# shield_schematic.net
KiCad netlist of a schematic drawn in EAGLE
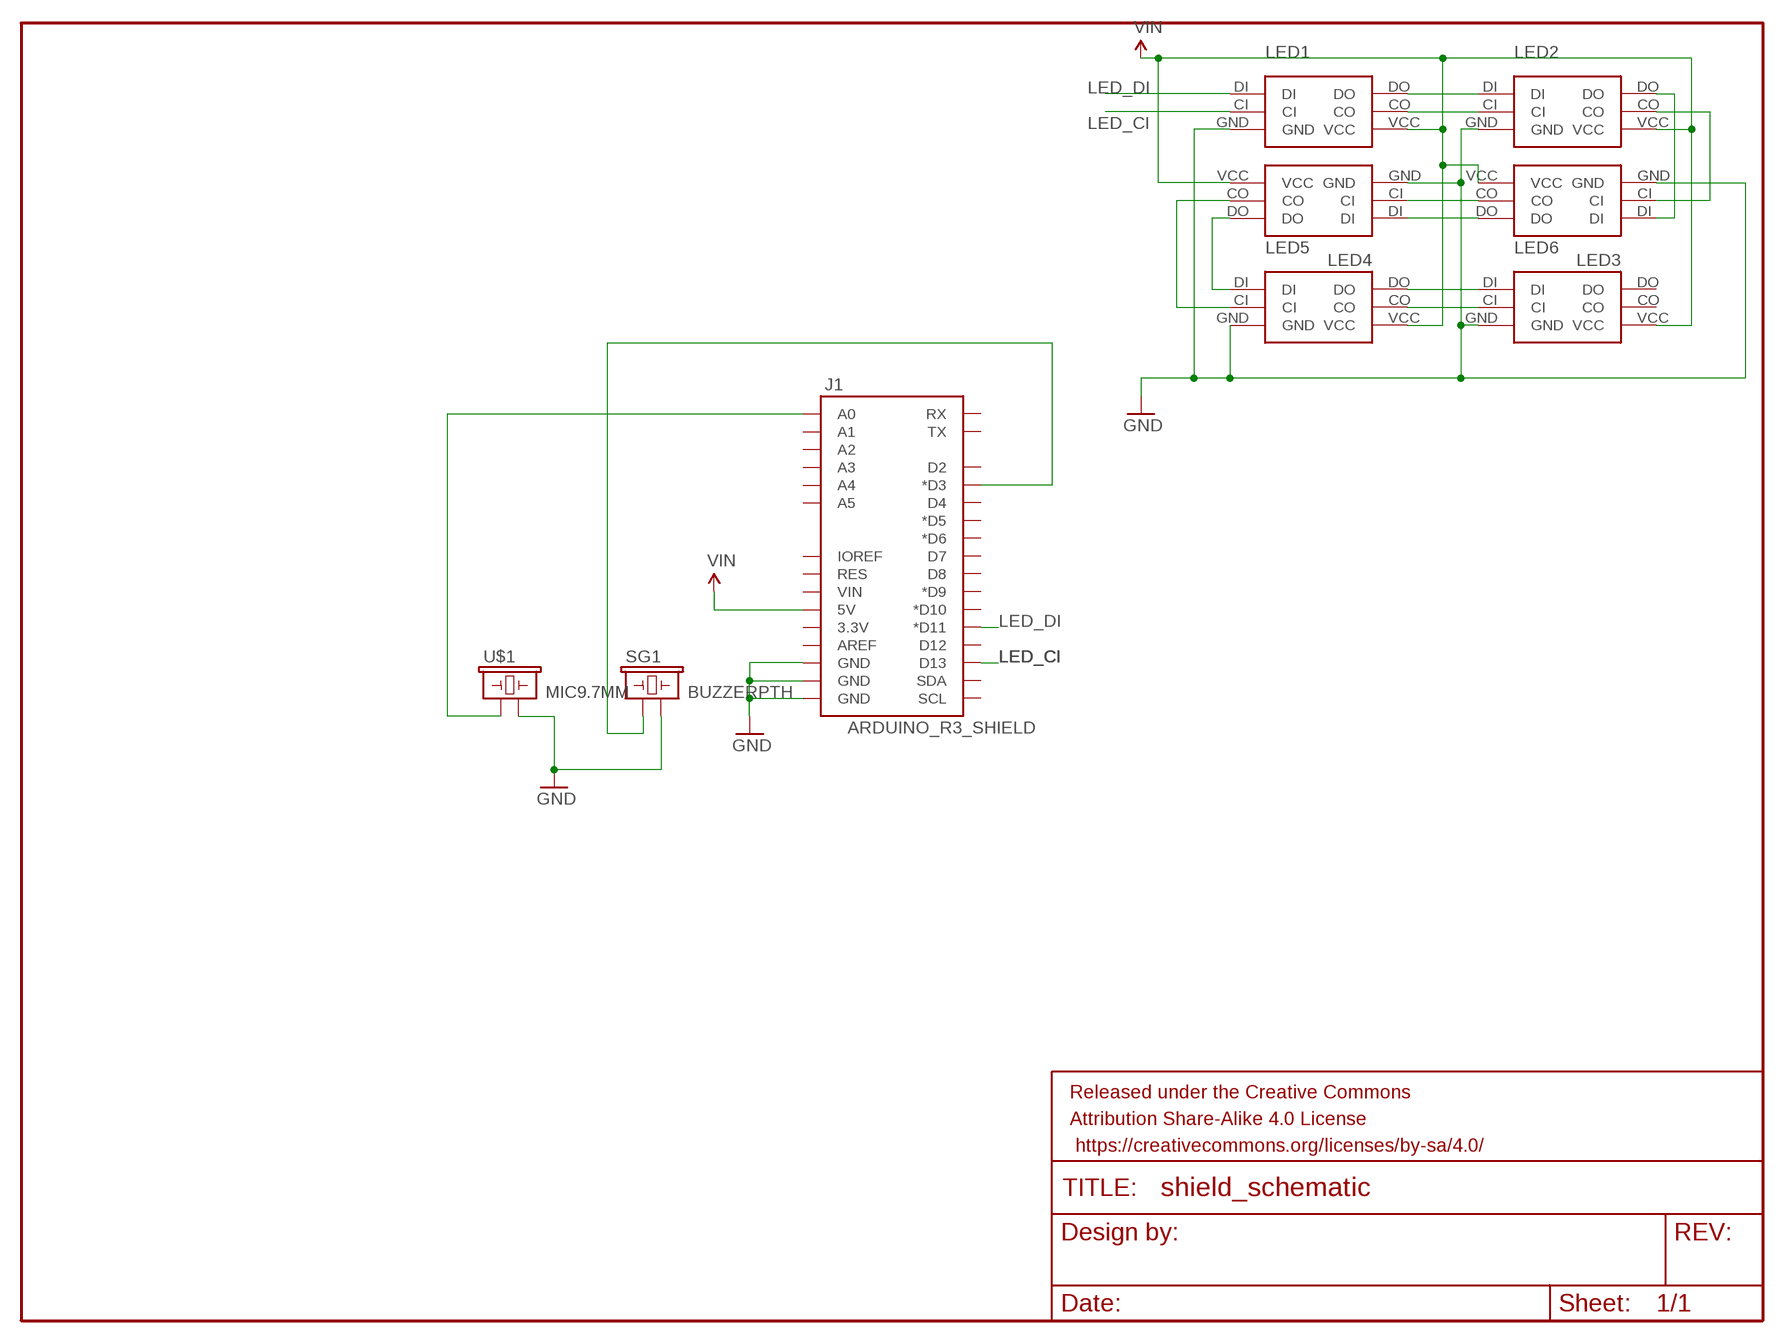
[diagram p0: schematic, sheet 1]

(export (version "E")
  (design (tool "Eeschema 10.0.6"))
  (components
    (comp (ref "FRAME1")
      (value "FRAME-LETTER")
      (footprint "eagle-import:CREATIVE_COMMONS")
      (libsource (lib "eagle-import") (part "FRAME-LETTER"))
    )
    (comp (ref "J1")
      (value "ARDUINO_R3_SHIELD")
      (footprint "eagle-import:UNO_R3_SHIELD")
      (libsource (lib "eagle-import") (part "ARDUINO_R3_SHIELD"))
    )
    (comp (ref "LED1")
      (value "APA102SMD")
      (footprint "eagle-import:RGBLED5050")
      (libsource (lib "eagle-import") (part "APA102SMD"))
    )
    (comp (ref "LED2")
      (value "APA102SMD")
      (footprint "eagle-import:RGBLED5050")
      (libsource (lib "eagle-import") (part "APA102SMD"))
    )
    (comp (ref "LED3")
      (value "APA102SMD")
      (footprint "eagle-import:RGBLED5050")
      (libsource (lib "eagle-import") (part "APA102SMD"))
    )
    (comp (ref "LED4")
      (value "APA102SMD")
      (footprint "eagle-import:RGBLED5050")
      (libsource (lib "eagle-import") (part "APA102SMD"))
    )
    (comp (ref "LED5")
      (value "APA102SMD")
      (footprint "eagle-import:RGBLED5050")
      (libsource (lib "eagle-import") (part "APA102SMD"))
    )
    (comp (ref "LED6")
      (value "APA102SMD")
      (footprint "eagle-import:RGBLED5050")
      (libsource (lib "eagle-import") (part "APA102SMD"))
    )
    (comp (ref "SG1")
      (value "BUZZERPTH")
      (footprint "eagle-import:BUZZER-12MM")
      (libsource (lib "eagle-import") (part "BUZZERPTH"))
    )
    (comp (ref "U$1")
      (value "MIC9.7MM")
      (footprint "eagle-import:MIC-9.7MM")
      (libsource (lib "eagle-import") (part "MIC9.7MM"))
    )
  )
  (nets
    (net (code "1") (name "/LED_CI") (class "Default")
      (node (ref "J1") (pin "D13") (pinfunction "D13_D13") (pintype "bidirectional"))
      (node (ref "LED1") (pin "CI") (pinfunction "CI_CI") (pintype "bidirectional"))
    )
    (net (code "2") (name "/LED_DI") (class "Default")
      (node (ref "J1") (pin "D11") (pinfunction "*D11_D11") (pintype "bidirectional"))
      (node (ref "LED1") (pin "DI") (pinfunction "DI_DI") (pintype "bidirectional"))
    )
    (net (code "3") (name "GND") (class "Default")
      (node (ref "J1") (pin "GND@0") (pinfunction "GND_GND@0") (pintype "bidirectional"))
      (node (ref "J1") (pin "GND@1") (pinfunction "GND_GND@1") (pintype "bidirectional"))
      (node (ref "J1") (pin "GND@2") (pinfunction "GND_GND@2") (pintype "bidirectional"))
      (node (ref "LED1") (pin "GND") (pinfunction "GND_GND") (pintype "bidirectional"))
      (node (ref "LED2") (pin "GND") (pinfunction "GND_GND") (pintype "bidirectional"))
      (node (ref "LED3") (pin "GND") (pinfunction "GND_GND") (pintype "bidirectional"))
      (node (ref "LED4") (pin "GND") (pinfunction "GND_GND") (pintype "bidirectional"))
      (node (ref "LED5") (pin "GND") (pinfunction "GND_GND") (pintype "bidirectional"))
      (node (ref "LED6") (pin "GND") (pinfunction "GND_GND") (pintype "bidirectional"))
      (node (ref "SG1") (pin "-") (pinfunction "2_-") (pintype "passive"))
      (node (ref "U$1") (pin "2") (pinfunction "2_2") (pintype "passive"))
    )
    (net (code "4") (name "Net-(J1-*D3)") (class "Default")
      (node (ref "J1") (pin "D3") (pinfunction "*D3_D3") (pintype "bidirectional"))
      (node (ref "SG1") (pin "+") (pinfunction "1_+") (pintype "passive"))
    )
    (net (code "5") (name "Net-(J1-PadA0)") (class "Default")
      (node (ref "J1") (pin "A0") (pinfunction "A0_A0") (pintype "bidirectional"))
      (node (ref "U$1") (pin "1") (pinfunction "1_1") (pintype "passive"))
    )
    (net (code "6") (name "Net-(LED1-PadCO)") (class "Default")
      (node (ref "LED1") (pin "CO") (pinfunction "CO_CO") (pintype "bidirectional"))
      (node (ref "LED2") (pin "CI") (pinfunction "CI_CI") (pintype "bidirectional"))
    )
    (net (code "7") (name "Net-(LED1-PadDO)") (class "Default")
      (node (ref "LED1") (pin "DO") (pinfunction "DO_DO") (pintype "bidirectional"))
      (node (ref "LED2") (pin "DI") (pinfunction "DI_DI") (pintype "bidirectional"))
    )
    (net (code "8") (name "Net-(LED2-PadCO)") (class "Default")
      (node (ref "LED2") (pin "CO") (pinfunction "CO_CO") (pintype "bidirectional"))
      (node (ref "LED3") (pin "CI") (pinfunction "CI_CI") (pintype "bidirectional"))
    )
    (net (code "9") (name "Net-(LED2-PadDO)") (class "Default")
      (node (ref "LED2") (pin "DO") (pinfunction "DO_DO") (pintype "bidirectional"))
      (node (ref "LED3") (pin "DI") (pinfunction "DI_DI") (pintype "bidirectional"))
    )
    (net (code "10") (name "Net-(LED3-PadCO)") (class "Default")
      (node (ref "LED3") (pin "CO") (pinfunction "CO_CO") (pintype "bidirectional"))
      (node (ref "LED4") (pin "CI") (pinfunction "CI_CI") (pintype "bidirectional"))
    )
    (net (code "11") (name "Net-(LED3-PadDO)") (class "Default")
      (node (ref "LED3") (pin "DO") (pinfunction "DO_DO") (pintype "bidirectional"))
      (node (ref "LED4") (pin "DI") (pinfunction "DI_DI") (pintype "bidirectional"))
    )
    (net (code "12") (name "Net-(LED4-PadCO)") (class "Default")
      (node (ref "LED4") (pin "CO") (pinfunction "CO_CO") (pintype "bidirectional"))
      (node (ref "LED5") (pin "CI") (pinfunction "CI_CI") (pintype "bidirectional"))
    )
    (net (code "13") (name "Net-(LED4-PadDO)") (class "Default")
      (node (ref "LED4") (pin "DO") (pinfunction "DO_DO") (pintype "bidirectional"))
      (node (ref "LED5") (pin "DI") (pinfunction "DI_DI") (pintype "bidirectional"))
    )
    (net (code "14") (name "Net-(LED5-PadCO)") (class "Default")
      (node (ref "LED5") (pin "CO") (pinfunction "CO_CO") (pintype "bidirectional"))
      (node (ref "LED6") (pin "CI") (pinfunction "CI_CI") (pintype "bidirectional"))
    )
    (net (code "15") (name "Net-(LED5-PadDO)") (class "Default")
      (node (ref "LED5") (pin "DO") (pinfunction "DO_DO") (pintype "bidirectional"))
      (node (ref "LED6") (pin "DI") (pinfunction "DI_DI") (pintype "bidirectional"))
    )
    (net (code "16") (name "VIN") (class "Default")
      (node (ref "J1") (pin "5V") (pinfunction "5V_5V") (pintype "bidirectional"))
      (node (ref "LED1") (pin "VCC") (pinfunction "VCC_VCC") (pintype "bidirectional"))
      (node (ref "LED2") (pin "VCC") (pinfunction "VCC_VCC") (pintype "bidirectional"))
      (node (ref "LED3") (pin "VCC") (pinfunction "VCC_VCC") (pintype "bidirectional"))
      (node (ref "LED4") (pin "VCC") (pinfunction "VCC_VCC") (pintype "bidirectional"))
      (node (ref "LED5") (pin "VCC") (pinfunction "VCC_VCC") (pintype "bidirectional"))
      (node (ref "LED6") (pin "VCC") (pinfunction "VCC_VCC") (pintype "bidirectional"))
    )
    (net (code "17") (name "unconnected-(J1-*D5-PadD5)") (class "Default")
      (node (ref "J1") (pin "D5") (pinfunction "*D5_D5") (pintype "bidirectional"))
    )
    (net (code "18") (name "unconnected-(J1-*D6-PadD6)") (class "Default")
      (node (ref "J1") (pin "D6") (pinfunction "*D6_D6") (pintype "bidirectional"))
    )
    (net (code "19") (name "unconnected-(J1-*D9-PadD9)") (class "Default")
      (node (ref "J1") (pin "D9") (pinfunction "*D9_D9") (pintype "bidirectional"))
    )
    (net (code "20") (name "unconnected-(J1-*D10-PadD10)") (class "Default")
      (node (ref "J1") (pin "D10") (pinfunction "*D10_D10") (pintype "bidirectional"))
    )
    (net (code "21") (name "unconnected-(J1-Pad3.3V)") (class "Default")
      (node (ref "J1") (pin "3.3V") (pinfunction "3.3V_3.3V") (pintype "bidirectional"))
    )
    (net (code "22") (name "unconnected-(J1-PadA1)") (class "Default")
      (node (ref "J1") (pin "A1") (pinfunction "A1_A1") (pintype "bidirectional"))
    )
    (net (code "23") (name "unconnected-(J1-PadA2)") (class "Default")
      (node (ref "J1") (pin "A2") (pinfunction "A2_A2") (pintype "bidirectional"))
    )
    (net (code "24") (name "unconnected-(J1-PadA3)") (class "Default")
      (node (ref "J1") (pin "A3") (pinfunction "A3_A3") (pintype "bidirectional"))
    )
    (net (code "25") (name "unconnected-(J1-PadA4)") (class "Default")
      (node (ref "J1") (pin "A4") (pinfunction "A4_A4") (pintype "bidirectional"))
    )
    (net (code "26") (name "unconnected-(J1-PadA5)") (class "Default")
      (node (ref "J1") (pin "A5") (pinfunction "A5_A5") (pintype "bidirectional"))
    )
    (net (code "27") (name "unconnected-(J1-PadAREF)") (class "Default")
      (node (ref "J1") (pin "AREF") (pinfunction "AREF_AREF") (pintype "bidirectional"))
    )
    (net (code "28") (name "unconnected-(J1-PadD2)") (class "Default")
      (node (ref "J1") (pin "D2") (pinfunction "D2_D2") (pintype "bidirectional"))
    )
    (net (code "29") (name "unconnected-(J1-PadD4)") (class "Default")
      (node (ref "J1") (pin "D4") (pinfunction "D4_D4") (pintype "bidirectional"))
    )
    (net (code "30") (name "unconnected-(J1-PadD7)") (class "Default")
      (node (ref "J1") (pin "D7") (pinfunction "D7_D7") (pintype "bidirectional"))
    )
    (net (code "31") (name "unconnected-(J1-PadD8)") (class "Default")
      (node (ref "J1") (pin "D8") (pinfunction "D8_D8") (pintype "bidirectional"))
    )
    (net (code "32") (name "unconnected-(J1-PadD12)") (class "Default")
      (node (ref "J1") (pin "D12") (pinfunction "D12_D12") (pintype "bidirectional"))
    )
    (net (code "33") (name "unconnected-(J1-PadIOREF)") (class "Default")
      (node (ref "J1") (pin "IOREF") (pinfunction "IOREF_IOREF") (pintype "bidirectional"))
    )
    (net (code "34") (name "unconnected-(J1-PadRES)") (class "Default")
      (node (ref "J1") (pin "RES") (pinfunction "RES_RES") (pintype "bidirectional"))
    )
    (net (code "35") (name "unconnected-(J1-PadRX)") (class "Default")
      (node (ref "J1") (pin "RX") (pinfunction "RX_RX") (pintype "bidirectional"))
    )
    (net (code "36") (name "unconnected-(J1-PadSCL)") (class "Default")
      (node (ref "J1") (pin "SCL") (pinfunction "SCL_SCL") (pintype "bidirectional"))
    )
    (net (code "37") (name "unconnected-(J1-PadSDA)") (class "Default")
      (node (ref "J1") (pin "SDA") (pinfunction "SDA_SDA") (pintype "bidirectional"))
    )
    (net (code "38") (name "unconnected-(J1-PadTX)") (class "Default")
      (node (ref "J1") (pin "TX") (pinfunction "TX_TX") (pintype "bidirectional"))
    )
    (net (code "39") (name "unconnected-(J1-PadVIN)") (class "Default")
      (node (ref "J1") (pin "VIN") (pinfunction "VIN_VIN") (pintype "bidirectional"))
    )
    (net (code "40") (name "unconnected-(LED6-PadCO)") (class "Default")
      (node (ref "LED6") (pin "CO") (pinfunction "CO_CO") (pintype "bidirectional"))
    )
    (net (code "41") (name "unconnected-(LED6-PadDO)") (class "Default")
      (node (ref "LED6") (pin "DO") (pinfunction "DO_DO") (pintype "bidirectional"))
    )
  )
)
